# Schematic.net
KiCad netlist of a schematic drawn in Altium Designer
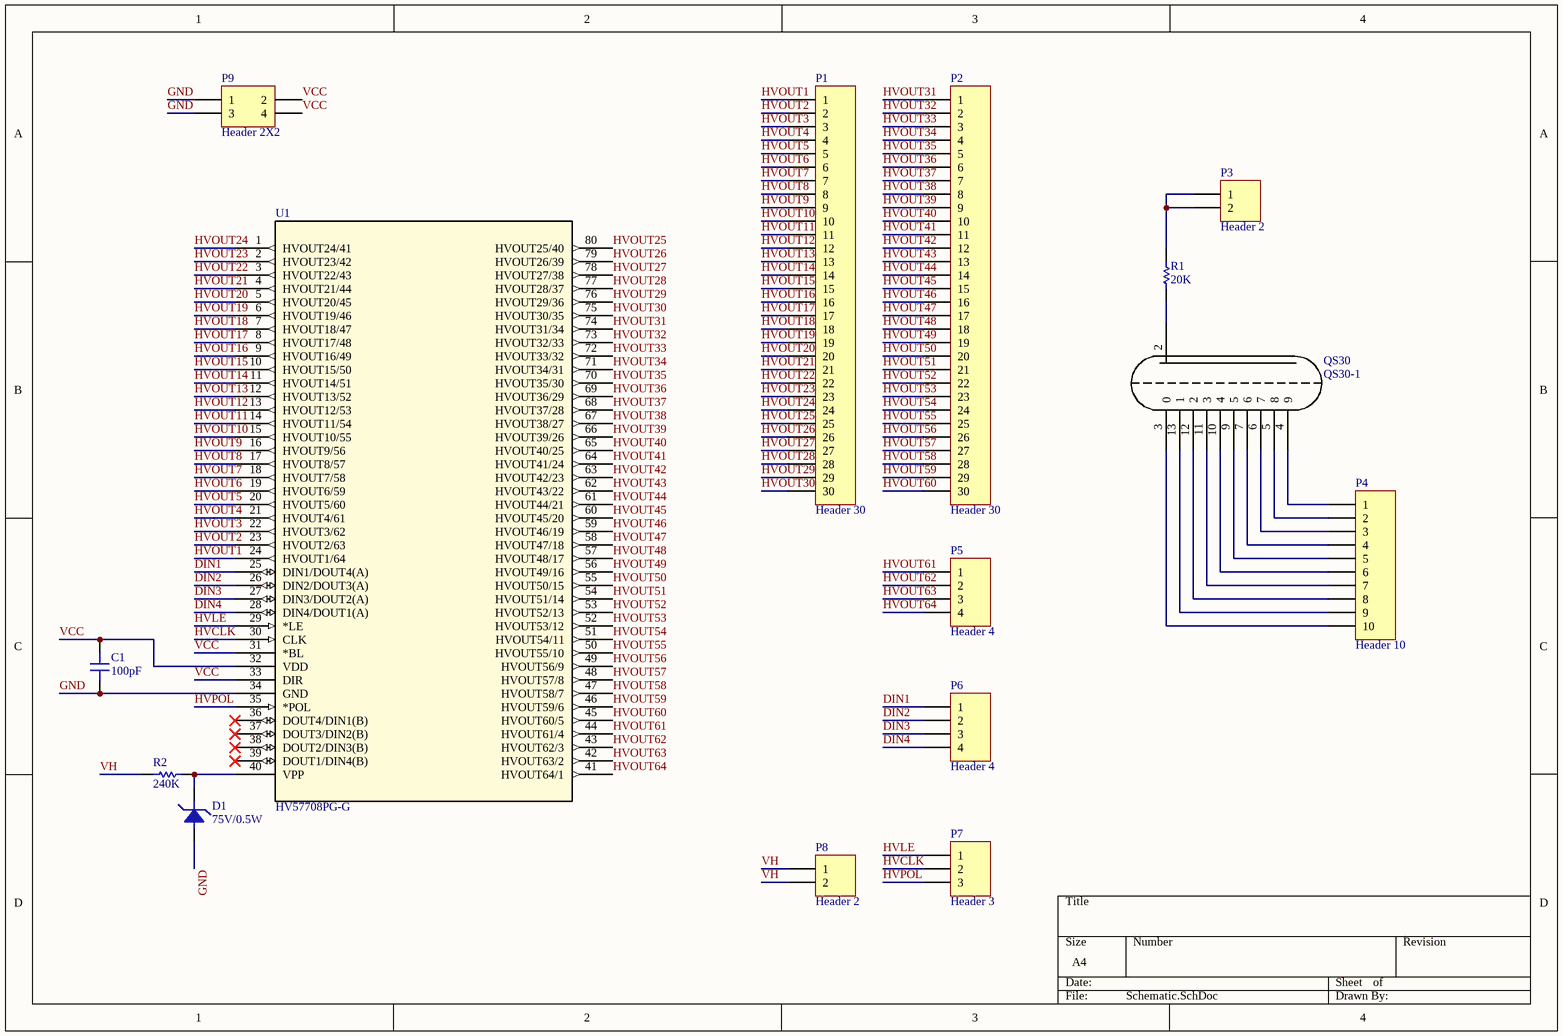
[diagram p0: Schematic.SchDoc]

(export (version "E")
  (design (tool "Eeschema 10.0.6"))
  (components
    (comp (ref "C1") (value "100pF") (footprint "0805") (libsource (lib "Basic") (part "Capacitor")))
    (comp (ref "D1")
      (value "75V/0.5W")
      (footprint "1206 Semiconductor")
      (libsource (lib "Basic") (part "DiodeZener"))
    )
    (comp (ref "P1")
      (value "Header 30")
      (footprint "HDR1X30")
      (description "Header, 30-Pin")
      (fields (field (name "PUBLISHER") "Altium Limited"))
      (libsource (lib "Connector") (part "Header 30"))
    )
    (comp (ref "P2")
      (value "Header 30")
      (footprint "HDR1X30")
      (description "Header, 30-Pin")
      (fields (field (name "PUBLISHER") "Altium Limited"))
      (libsource (lib "Connector") (part "Header 30"))
    )
    (comp (ref "P3")
      (value "Header 2")
      (footprint "HDR1X2")
      (description "Header, 2-Pin")
      (fields (field (name "PUBLISHER") "Altium Limited"))
      (libsource (lib "Connector") (part "Header 2"))
    )
    (comp (ref "P4")
      (value "Header 10")
      (footprint "HDR1X10")
      (description "Header, 10-Pin")
      (fields (field (name "PUBLISHER") "Altium Limited"))
      (libsource (lib "Connector") (part "Header 10"))
    )
    (comp (ref "P5")
      (value "Header 4")
      (footprint "HDR1X4")
      (description "Header, 4-Pin")
      (fields (field (name "PUBLISHER") "Altium Limited"))
      (libsource (lib "Connector") (part "Header 4"))
    )
    (comp (ref "P6")
      (value "Header 4")
      (footprint "HDR1X4")
      (description "Header, 4-Pin")
      (fields (field (name "PUBLISHER") "Altium Limited"))
      (libsource (lib "Connector") (part "Header 4"))
    )
    (comp (ref "P7")
      (value "Header 3")
      (footprint "HDR1X3")
      (description "Header, 3-Pin")
      (fields (field (name "PUBLISHER") "Altium Limited"))
      (libsource (lib "Connector") (part "Header 3"))
    )
    (comp (ref "P8")
      (value "Header 2")
      (footprint "HDR1X2")
      (description "Header, 2-Pin")
      (fields (field (name "PUBLISHER") "Altium Limited"))
      (libsource (lib "Connector") (part "Header 2"))
    )
    (comp (ref "P9")
      (value "Header 2X2")
      (footprint "HDR2X2")
      (description "Header, 2-Pin, Dual row")
      (fields (field (name "PUBLISHER") "Altium Limited"))
      (libsource (lib "Connector") (part "Header 2X2"))
    )
    (comp (ref "QS30") (value "QS30-1") (footprint "QS30-1") (libsource (lib "Connector") (part "QS30-1")))
    (comp (ref "R1") (value "20K") (footprint "0805") (libsource (lib "Basic") (part "Resistor")))
    (comp (ref "R2") (value "240K") (footprint "0805") (libsource (lib "Basic") (part "Resistor")))
    (comp (ref "U1")
      (value "HV57708PG-G")
      (footprint "PQFP80_20X14MC_MCH")
      (description "No Description Available")
      (libsource (lib "Ic") (part "HV57708PG-G"))
    )
  )
  (nets
    (net (code "1") (name "/DIN1") (class "Default")
      (node (ref "P6") (pin "1") (pinfunction "1_1") (pintype "passive"))
      (node (ref "U1") (pin "25") (pinfunction "DIN1/DOUT4(A)_25") (pintype "bidirectional"))
    )
    (net (code "2") (name "/DIN2") (class "Default")
      (node (ref "P6") (pin "2") (pinfunction "2_2") (pintype "passive"))
      (node (ref "U1") (pin "26") (pinfunction "DIN2/DOUT3(A)_26") (pintype "bidirectional"))
    )
    (net (code "3") (name "/DIN3") (class "Default")
      (node (ref "P6") (pin "3") (pinfunction "3_3") (pintype "passive"))
      (node (ref "U1") (pin "27") (pinfunction "DIN3/DOUT2(A)_27") (pintype "bidirectional"))
    )
    (net (code "4") (name "/DIN4") (class "Default")
      (node (ref "P6") (pin "4") (pinfunction "4_4") (pintype "passive"))
      (node (ref "U1") (pin "28") (pinfunction "DIN4/DOUT1(A)_28") (pintype "bidirectional"))
    )
    (net (code "5") (name "/GND") (class "Default")
      (node (ref "C1") (pin "1") (pinfunction "1_1") (pintype "passive"))
      (node (ref "D1") (pin "2") (pinfunction "2_2") (pintype "passive"))
      (node (ref "P9") (pin "1") (pinfunction "1_1") (pintype "passive"))
      (node (ref "P9") (pin "3") (pinfunction "3_3") (pintype "passive"))
      (node (ref "U1") (pin "34") (pinfunction "GND_34") (pintype "power_in"))
    )
    (net (code "6") (name "/HVCLK") (class "Default")
      (node (ref "P7") (pin "2") (pinfunction "2_2") (pintype "passive"))
      (node (ref "U1") (pin "30") (pinfunction "CLK_30") (pintype "input"))
    )
    (net (code "7") (name "/HVLE") (class "Default")
      (node (ref "P7") (pin "1") (pinfunction "1_1") (pintype "passive"))
      (node (ref "U1") (pin "29") (pinfunction "*LE_29") (pintype "input"))
    )
    (net (code "8") (name "/HVOUT1") (class "Default")
      (node (ref "P1") (pin "1") (pinfunction "1_1") (pintype "passive"))
      (node (ref "U1") (pin "24") (pinfunction "HVOUT1/64_24") (pintype "output"))
    )
    (net (code "9") (name "/HVOUT2") (class "Default")
      (node (ref "P1") (pin "2") (pinfunction "2_2") (pintype "passive"))
      (node (ref "U1") (pin "23") (pinfunction "HVOUT2/63_23") (pintype "output"))
    )
    (net (code "10") (name "/HVOUT3") (class "Default")
      (node (ref "P1") (pin "3") (pinfunction "3_3") (pintype "passive"))
      (node (ref "U1") (pin "22") (pinfunction "HVOUT3/62_22") (pintype "output"))
    )
    (net (code "11") (name "/HVOUT4") (class "Default")
      (node (ref "P1") (pin "4") (pinfunction "4_4") (pintype "passive"))
      (node (ref "U1") (pin "21") (pinfunction "HVOUT4/61_21") (pintype "output"))
    )
    (net (code "12") (name "/HVOUT5") (class "Default")
      (node (ref "P1") (pin "5") (pinfunction "5_5") (pintype "passive"))
      (node (ref "U1") (pin "20") (pinfunction "HVOUT5/60_20") (pintype "output"))
    )
    (net (code "13") (name "/HVOUT6") (class "Default")
      (node (ref "P1") (pin "6") (pinfunction "6_6") (pintype "passive"))
      (node (ref "U1") (pin "19") (pinfunction "HVOUT6/59_19") (pintype "output"))
    )
    (net (code "14") (name "/HVOUT7") (class "Default")
      (node (ref "P1") (pin "7") (pinfunction "7_7") (pintype "passive"))
      (node (ref "U1") (pin "18") (pinfunction "HVOUT7/58_18") (pintype "output"))
    )
    (net (code "15") (name "/HVOUT8") (class "Default")
      (node (ref "P1") (pin "8") (pinfunction "8_8") (pintype "passive"))
      (node (ref "U1") (pin "17") (pinfunction "HVOUT8/57_17") (pintype "output"))
    )
    (net (code "16") (name "/HVOUT9") (class "Default")
      (node (ref "P1") (pin "9") (pinfunction "9_9") (pintype "passive"))
      (node (ref "U1") (pin "16") (pinfunction "HVOUT9/56_16") (pintype "output"))
    )
    (net (code "17") (name "/HVOUT10") (class "Default")
      (node (ref "P1") (pin "10") (pinfunction "10_10") (pintype "passive"))
      (node (ref "U1") (pin "15") (pinfunction "HVOUT10/55_15") (pintype "output"))
    )
    (net (code "18") (name "/HVOUT11") (class "Default")
      (node (ref "P1") (pin "11") (pinfunction "11_11") (pintype "passive"))
      (node (ref "U1") (pin "14") (pinfunction "HVOUT11/54_14") (pintype "output"))
    )
    (net (code "19") (name "/HVOUT12") (class "Default")
      (node (ref "P1") (pin "12") (pinfunction "12_12") (pintype "passive"))
      (node (ref "U1") (pin "13") (pinfunction "HVOUT12/53_13") (pintype "output"))
    )
    (net (code "20") (name "/HVOUT13") (class "Default")
      (node (ref "P1") (pin "13") (pinfunction "13_13") (pintype "passive"))
      (node (ref "U1") (pin "12") (pinfunction "HVOUT13/52_12") (pintype "output"))
    )
    (net (code "21") (name "/HVOUT14") (class "Default")
      (node (ref "P1") (pin "14") (pinfunction "14_14") (pintype "passive"))
      (node (ref "U1") (pin "11") (pinfunction "HVOUT14/51_11") (pintype "output"))
    )
    (net (code "22") (name "/HVOUT15") (class "Default")
      (node (ref "P1") (pin "15") (pinfunction "15_15") (pintype "passive"))
      (node (ref "U1") (pin "10") (pinfunction "HVOUT15/50_10") (pintype "output"))
    )
    (net (code "23") (name "/HVOUT16") (class "Default")
      (node (ref "P1") (pin "16") (pinfunction "16_16") (pintype "passive"))
      (node (ref "U1") (pin "9") (pinfunction "HVOUT16/49_9") (pintype "output"))
    )
    (net (code "24") (name "/HVOUT17") (class "Default")
      (node (ref "P1") (pin "17") (pinfunction "17_17") (pintype "passive"))
      (node (ref "U1") (pin "8") (pinfunction "HVOUT17/48_8") (pintype "output"))
    )
    (net (code "25") (name "/HVOUT18") (class "Default")
      (node (ref "P1") (pin "18") (pinfunction "18_18") (pintype "passive"))
      (node (ref "U1") (pin "7") (pinfunction "HVOUT18/47_7") (pintype "output"))
    )
    (net (code "26") (name "/HVOUT19") (class "Default")
      (node (ref "P1") (pin "19") (pinfunction "19_19") (pintype "passive"))
      (node (ref "U1") (pin "6") (pinfunction "HVOUT19/46_6") (pintype "output"))
    )
    (net (code "27") (name "/HVOUT20") (class "Default")
      (node (ref "P1") (pin "20") (pinfunction "20_20") (pintype "passive"))
      (node (ref "U1") (pin "5") (pinfunction "HVOUT20/45_5") (pintype "output"))
    )
    (net (code "28") (name "/HVOUT21") (class "Default")
      (node (ref "P1") (pin "21") (pinfunction "21_21") (pintype "passive"))
      (node (ref "U1") (pin "4") (pinfunction "HVOUT21/44_4") (pintype "output"))
    )
    (net (code "29") (name "/HVOUT22") (class "Default")
      (node (ref "P1") (pin "22") (pinfunction "22_22") (pintype "passive"))
      (node (ref "U1") (pin "3") (pinfunction "HVOUT22/43_3") (pintype "output"))
    )
    (net (code "30") (name "/HVOUT23") (class "Default")
      (node (ref "P1") (pin "23") (pinfunction "23_23") (pintype "passive"))
      (node (ref "U1") (pin "2") (pinfunction "HVOUT23/42_2") (pintype "output"))
    )
    (net (code "31") (name "/HVOUT24") (class "Default")
      (node (ref "P1") (pin "24") (pinfunction "24_24") (pintype "passive"))
      (node (ref "U1") (pin "1") (pinfunction "HVOUT24/41_1") (pintype "output"))
    )
    (net (code "32") (name "/HVOUT25") (class "Default")
      (node (ref "P1") (pin "25") (pinfunction "25_25") (pintype "passive"))
      (node (ref "U1") (pin "80") (pinfunction "HVOUT25/40_80") (pintype "output"))
    )
    (net (code "33") (name "/HVOUT26") (class "Default")
      (node (ref "P1") (pin "26") (pinfunction "26_26") (pintype "passive"))
      (node (ref "U1") (pin "79") (pinfunction "HVOUT26/39_79") (pintype "output"))
    )
    (net (code "34") (name "/HVOUT27") (class "Default")
      (node (ref "P1") (pin "27") (pinfunction "27_27") (pintype "passive"))
      (node (ref "U1") (pin "78") (pinfunction "HVOUT27/38_78") (pintype "output"))
    )
    (net (code "35") (name "/HVOUT28") (class "Default")
      (node (ref "P1") (pin "28") (pinfunction "28_28") (pintype "passive"))
      (node (ref "U1") (pin "77") (pinfunction "HVOUT28/37_77") (pintype "output"))
    )
    (net (code "36") (name "/HVOUT29") (class "Default")
      (node (ref "P1") (pin "29") (pinfunction "29_29") (pintype "passive"))
      (node (ref "U1") (pin "76") (pinfunction "HVOUT29/36_76") (pintype "output"))
    )
    (net (code "37") (name "/HVOUT30") (class "Default")
      (node (ref "P1") (pin "30") (pinfunction "30_30") (pintype "passive"))
      (node (ref "U1") (pin "75") (pinfunction "HVOUT30/35_75") (pintype "output"))
    )
    (net (code "38") (name "/HVOUT31") (class "Default")
      (node (ref "P2") (pin "1") (pinfunction "1_1") (pintype "passive"))
      (node (ref "U1") (pin "74") (pinfunction "HVOUT31/34_74") (pintype "output"))
    )
    (net (code "39") (name "/HVOUT32") (class "Default")
      (node (ref "P2") (pin "2") (pinfunction "2_2") (pintype "passive"))
      (node (ref "U1") (pin "73") (pinfunction "HVOUT32/33_73") (pintype "output"))
    )
    (net (code "40") (name "/HVOUT33") (class "Default")
      (node (ref "P2") (pin "3") (pinfunction "3_3") (pintype "passive"))
      (node (ref "U1") (pin "72") (pinfunction "HVOUT33/32_72") (pintype "output"))
    )
    (net (code "41") (name "/HVOUT34") (class "Default")
      (node (ref "P2") (pin "4") (pinfunction "4_4") (pintype "passive"))
      (node (ref "U1") (pin "71") (pinfunction "HVOUT34/31_71") (pintype "output"))
    )
    (net (code "42") (name "/HVOUT35") (class "Default")
      (node (ref "P2") (pin "5") (pinfunction "5_5") (pintype "passive"))
      (node (ref "U1") (pin "70") (pinfunction "HVOUT35/30_70") (pintype "output"))
    )
    (net (code "43") (name "/HVOUT36") (class "Default")
      (node (ref "P2") (pin "6") (pinfunction "6_6") (pintype "passive"))
      (node (ref "U1") (pin "69") (pinfunction "HVOUT36/29_69") (pintype "output"))
    )
    (net (code "44") (name "/HVOUT37") (class "Default")
      (node (ref "P2") (pin "7") (pinfunction "7_7") (pintype "passive"))
      (node (ref "U1") (pin "68") (pinfunction "HVOUT37/28_68") (pintype "output"))
    )
    (net (code "45") (name "/HVOUT38") (class "Default")
      (node (ref "P2") (pin "8") (pinfunction "8_8") (pintype "passive"))
      (node (ref "U1") (pin "67") (pinfunction "HVOUT38/27_67") (pintype "output"))
    )
    (net (code "46") (name "/HVOUT39") (class "Default")
      (node (ref "P2") (pin "9") (pinfunction "9_9") (pintype "passive"))
      (node (ref "U1") (pin "66") (pinfunction "HVOUT39/26_66") (pintype "output"))
    )
    (net (code "47") (name "/HVOUT40") (class "Default")
      (node (ref "P2") (pin "10") (pinfunction "10_10") (pintype "passive"))
      (node (ref "U1") (pin "65") (pinfunction "HVOUT40/25_65") (pintype "output"))
    )
    (net (code "48") (name "/HVOUT41") (class "Default")
      (node (ref "P2") (pin "11") (pinfunction "11_11") (pintype "passive"))
      (node (ref "U1") (pin "64") (pinfunction "HVOUT41/24_64") (pintype "output"))
    )
    (net (code "49") (name "/HVOUT42") (class "Default")
      (node (ref "P2") (pin "12") (pinfunction "12_12") (pintype "passive"))
      (node (ref "U1") (pin "63") (pinfunction "HVOUT42/23_63") (pintype "output"))
    )
    (net (code "50") (name "/HVOUT43") (class "Default")
      (node (ref "P2") (pin "13") (pinfunction "13_13") (pintype "passive"))
      (node (ref "U1") (pin "62") (pinfunction "HVOUT43/22_62") (pintype "output"))
    )
    (net (code "51") (name "/HVOUT44") (class "Default")
      (node (ref "P2") (pin "14") (pinfunction "14_14") (pintype "passive"))
      (node (ref "U1") (pin "61") (pinfunction "HVOUT44/21_61") (pintype "output"))
    )
    (net (code "52") (name "/HVOUT45") (class "Default")
      (node (ref "P2") (pin "15") (pinfunction "15_15") (pintype "passive"))
      (node (ref "U1") (pin "60") (pinfunction "HVOUT45/20_60") (pintype "output"))
    )
    (net (code "53") (name "/HVOUT46") (class "Default")
      (node (ref "P2") (pin "16") (pinfunction "16_16") (pintype "passive"))
      (node (ref "U1") (pin "59") (pinfunction "HVOUT46/19_59") (pintype "output"))
    )
    (net (code "54") (name "/HVOUT47") (class "Default")
      (node (ref "P2") (pin "17") (pinfunction "17_17") (pintype "passive"))
      (node (ref "U1") (pin "58") (pinfunction "HVOUT47/18_58") (pintype "output"))
    )
    (net (code "55") (name "/HVOUT48") (class "Default")
      (node (ref "P2") (pin "18") (pinfunction "18_18") (pintype "passive"))
      (node (ref "U1") (pin "57") (pinfunction "HVOUT48/17_57") (pintype "output"))
    )
    (net (code "56") (name "/HVOUT49") (class "Default")
      (node (ref "P2") (pin "19") (pinfunction "19_19") (pintype "passive"))
      (node (ref "U1") (pin "56") (pinfunction "HVOUT49/16_56") (pintype "output"))
    )
    (net (code "57") (name "/HVOUT50") (class "Default")
      (node (ref "P2") (pin "20") (pinfunction "20_20") (pintype "passive"))
      (node (ref "U1") (pin "55") (pinfunction "HVOUT50/15_55") (pintype "output"))
    )
    (net (code "58") (name "/HVOUT51") (class "Default")
      (node (ref "P2") (pin "21") (pinfunction "21_21") (pintype "passive"))
      (node (ref "U1") (pin "54") (pinfunction "HVOUT51/14_54") (pintype "output"))
    )
    (net (code "59") (name "/HVOUT52") (class "Default")
      (node (ref "P2") (pin "22") (pinfunction "22_22") (pintype "passive"))
      (node (ref "U1") (pin "53") (pinfunction "HVOUT52/13_53") (pintype "output"))
    )
    (net (code "60") (name "/HVOUT53") (class "Default")
      (node (ref "P2") (pin "23") (pinfunction "23_23") (pintype "passive"))
      (node (ref "U1") (pin "52") (pinfunction "HVOUT53/12_52") (pintype "output"))
    )
    (net (code "61") (name "/HVOUT54") (class "Default")
      (node (ref "P2") (pin "24") (pinfunction "24_24") (pintype "passive"))
      (node (ref "U1") (pin "51") (pinfunction "HVOUT54/11_51") (pintype "output"))
    )
    (net (code "62") (name "/HVOUT55") (class "Default")
      (node (ref "P2") (pin "25") (pinfunction "25_25") (pintype "passive"))
      (node (ref "U1") (pin "50") (pinfunction "HVOUT55/10_50") (pintype "output"))
    )
    (net (code "63") (name "/HVOUT56") (class "Default")
      (node (ref "P2") (pin "26") (pinfunction "26_26") (pintype "passive"))
      (node (ref "U1") (pin "49") (pinfunction "HVOUT56/9_49") (pintype "output"))
    )
    (net (code "64") (name "/HVOUT57") (class "Default")
      (node (ref "P2") (pin "27") (pinfunction "27_27") (pintype "passive"))
      (node (ref "U1") (pin "48") (pinfunction "HVOUT57/8_48") (pintype "output"))
    )
    (net (code "65") (name "/HVOUT58") (class "Default")
      (node (ref "P2") (pin "28") (pinfunction "28_28") (pintype "passive"))
      (node (ref "U1") (pin "47") (pinfunction "HVOUT58/7_47") (pintype "output"))
    )
    (net (code "66") (name "/HVOUT59") (class "Default")
      (node (ref "P2") (pin "29") (pinfunction "29_29") (pintype "passive"))
      (node (ref "U1") (pin "46") (pinfunction "HVOUT59/6_46") (pintype "output"))
    )
    (net (code "67") (name "/HVOUT60") (class "Default")
      (node (ref "P2") (pin "30") (pinfunction "30_30") (pintype "passive"))
      (node (ref "U1") (pin "45") (pinfunction "HVOUT60/5_45") (pintype "output"))
    )
    (net (code "68") (name "/HVOUT61") (class "Default")
      (node (ref "P5") (pin "1") (pinfunction "1_1") (pintype "passive"))
      (node (ref "U1") (pin "44") (pinfunction "HVOUT61/4_44") (pintype "output"))
    )
    (net (code "69") (name "/HVOUT62") (class "Default")
      (node (ref "P5") (pin "2") (pinfunction "2_2") (pintype "passive"))
      (node (ref "U1") (pin "43") (pinfunction "HVOUT62/3_43") (pintype "output"))
    )
    (net (code "70") (name "/HVOUT63") (class "Default")
      (node (ref "P5") (pin "3") (pinfunction "3_3") (pintype "passive"))
      (node (ref "U1") (pin "42") (pinfunction "HVOUT63/2_42") (pintype "output"))
    )
    (net (code "71") (name "/HVOUT64") (class "Default")
      (node (ref "P5") (pin "4") (pinfunction "4_4") (pintype "passive"))
      (node (ref "U1") (pin "41") (pinfunction "HVOUT64/1_41") (pintype "output"))
    )
    (net (code "72") (name "/HVPOL") (class "Default")
      (node (ref "P7") (pin "3") (pinfunction "3_3") (pintype "passive"))
      (node (ref "U1") (pin "35") (pinfunction "*POL_35") (pintype "input"))
    )
    (net (code "73") (name "/VCC") (class "Default")
      (node (ref "C1") (pin "2") (pinfunction "2_2") (pintype "passive"))
      (node (ref "P9") (pin "2") (pinfunction "2_2") (pintype "passive"))
      (node (ref "P9") (pin "4") (pinfunction "4_4") (pintype "passive"))
      (node (ref "U1") (pin "31") (pinfunction "*BL_31") (pintype "passive"))
      (node (ref "U1") (pin "32") (pinfunction "VDD_32") (pintype "power_in"))
      (node (ref "U1") (pin "33") (pinfunction "DIR_33") (pintype "passive"))
    )
    (net (code "74") (name "/VH") (class "Default")
      (node (ref "P8") (pin "1") (pinfunction "1_1") (pintype "passive"))
      (node (ref "P8") (pin "2") (pinfunction "2_2") (pintype "passive"))
      (node (ref "R2") (pin "1") (pinfunction "1_1") (pintype "passive"))
    )
    (net (code "75") (name "Net-(P3-Pad1)") (class "Default")
      (node (ref "P3") (pin "1") (pinfunction "1_1") (pintype "passive"))
      (node (ref "P3") (pin "2") (pinfunction "2_2") (pintype "passive"))
      (node (ref "R1") (pin "1") (pinfunction "1_1") (pintype "passive"))
    )
    (net (code "76") (name "Net-(QS30-0)") (class "Default")
      (node (ref "P4") (pin "10") (pinfunction "10_10") (pintype "passive"))
      (node (ref "QS30") (pin "3") (pinfunction "0_3") (pintype "passive"))
    )
    (net (code "77") (name "Net-(QS30-1)") (class "Default")
      (node (ref "P4") (pin "9") (pinfunction "9_9") (pintype "passive"))
      (node (ref "QS30") (pin "13") (pinfunction "1_13") (pintype "passive"))
    )
    (net (code "78") (name "Net-(QS30-2)") (class "Default")
      (node (ref "P4") (pin "8") (pinfunction "8_8") (pintype "passive"))
      (node (ref "QS30") (pin "12") (pinfunction "2_12") (pintype "passive"))
    )
    (net (code "79") (name "Net-(QS30-3)") (class "Default")
      (node (ref "P4") (pin "7") (pinfunction "7_7") (pintype "passive"))
      (node (ref "QS30") (pin "11") (pinfunction "3_11") (pintype "passive"))
    )
    (net (code "80") (name "Net-(QS30-4)") (class "Default")
      (node (ref "P4") (pin "6") (pinfunction "6_6") (pintype "passive"))
      (node (ref "QS30") (pin "10") (pinfunction "4_10") (pintype "passive"))
    )
    (net (code "81") (name "Net-(QS30-5)") (class "Default")
      (node (ref "P4") (pin "5") (pinfunction "5_5") (pintype "passive"))
      (node (ref "QS30") (pin "9") (pinfunction "5_9") (pintype "passive"))
    )
    (net (code "82") (name "Net-(QS30-6)") (class "Default")
      (node (ref "P4") (pin "4") (pinfunction "4_4") (pintype "passive"))
      (node (ref "QS30") (pin "7") (pinfunction "6_7") (pintype "passive"))
    )
    (net (code "83") (name "Net-(QS30-7)") (class "Default")
      (node (ref "P4") (pin "3") (pinfunction "3_3") (pintype "passive"))
      (node (ref "QS30") (pin "6") (pinfunction "7_6") (pintype "passive"))
    )
    (net (code "84") (name "Net-(QS30-8)") (class "Default")
      (node (ref "P4") (pin "2") (pinfunction "2_2") (pintype "passive"))
      (node (ref "QS30") (pin "5") (pinfunction "8_5") (pintype "passive"))
    )
    (net (code "85") (name "Net-(QS30-9)") (class "Default")
      (node (ref "P4") (pin "1") (pinfunction "1_1") (pintype "passive"))
      (node (ref "QS30") (pin "4") (pinfunction "9_4") (pintype "passive"))
    )
    (net (code "86") (name "Net-(QS30-10)") (class "Default")
      (node (ref "QS30") (pin "2") (pinfunction "10_2") (pintype "passive"))
      (node (ref "R1") (pin "2") (pinfunction "2_2") (pintype "passive"))
    )
    (net (code "87") (name "Net-(U1-VPP)") (class "Default")
      (node (ref "D1") (pin "1") (pinfunction "1_1") (pintype "passive"))
      (node (ref "R2") (pin "2") (pinfunction "2_2") (pintype "passive"))
      (node (ref "U1") (pin "40") (pinfunction "VPP_40") (pintype "power_in"))
    )
    (net (code "88") (name "unconnected-(U1-DOUT1{slash}DIN4(B)-Pad39)") (class "Default")
      (node (ref "U1") (pin "39") (pinfunction "DOUT1/DIN4(B)_39") (pintype "bidirectional+no_connect"))
    )
    (net (code "89") (name "unconnected-(U1-DOUT2{slash}DIN3(B)-Pad38)") (class "Default")
      (node (ref "U1") (pin "38") (pinfunction "DOUT2/DIN3(B)_38") (pintype "bidirectional+no_connect"))
    )
    (net (code "90") (name "unconnected-(U1-DOUT3{slash}DIN2(B)-Pad37)") (class "Default")
      (node (ref "U1") (pin "37") (pinfunction "DOUT3/DIN2(B)_37") (pintype "bidirectional+no_connect"))
    )
    (net (code "91") (name "unconnected-(U1-DOUT4{slash}DIN1(B)-Pad36)") (class "Default")
      (node (ref "U1") (pin "36") (pinfunction "DOUT4/DIN1(B)_36") (pintype "bidirectional+no_connect"))
    )
  )
)
